# HeatBed.net
KiCad netlist of a schematic drawn in EAGLE
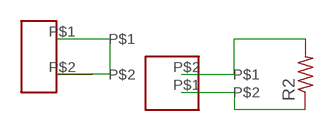
[diagram p0: schematic, sheet 1]

(export (version "E")
  (design (tool "Eeschema 10.0.6"))
  (components
    (comp (ref "R2")
      (value "R-US_R0402")
      (footprint "eagle-import:R0402")
      (libsource (lib "eagle-import") (part "R-US_R0402"))
    )
    (comp (ref "U$2")
      (value "SMD_WAFER_2")
      (footprint "eagle-import:SMD_WAFER_02")
      (libsource (lib "eagle-import") (part "SMD_WAFER_2"))
    )
    (comp (ref "U$3")
      (value "SMD_TERMINAL_2")
      (footprint "eagle-import:SMD_5MM_2")
      (libsource (lib "eagle-import") (part "SMD_TERMINAL_2"))
    )
  )
  (nets
    (net (code "1") (name "Net-(U$2-P$1)") (class "Default")
      (node (ref "R2") (pin "2") (pinfunction "2_2") (pintype "passive"))
      (node (ref "U$2") (pin "P$2") (pinfunction "P$1_P$2") (pintype "bidirectional"))
    )
    (net (code "2") (name "Net-(U$2-P$2)") (class "Default")
      (node (ref "R2") (pin "1") (pinfunction "1_1") (pintype "passive"))
      (node (ref "U$2") (pin "P$1") (pinfunction "P$2_P$1") (pintype "bidirectional"))
    )
    (net (code "3") (name "Net-(U$3-PadP$1)") (class "Default")
      (node (ref "U$3") (pin "P$1") (pinfunction "P$1_P$1") (pintype "bidirectional"))
      (node (ref "U$3") (pin "P$2") (pinfunction "P$2_P$2") (pintype "bidirectional"))
    )
  )
)
